# bc-cpu.net
KiCad netlist of a schematic drawn in EAGLE
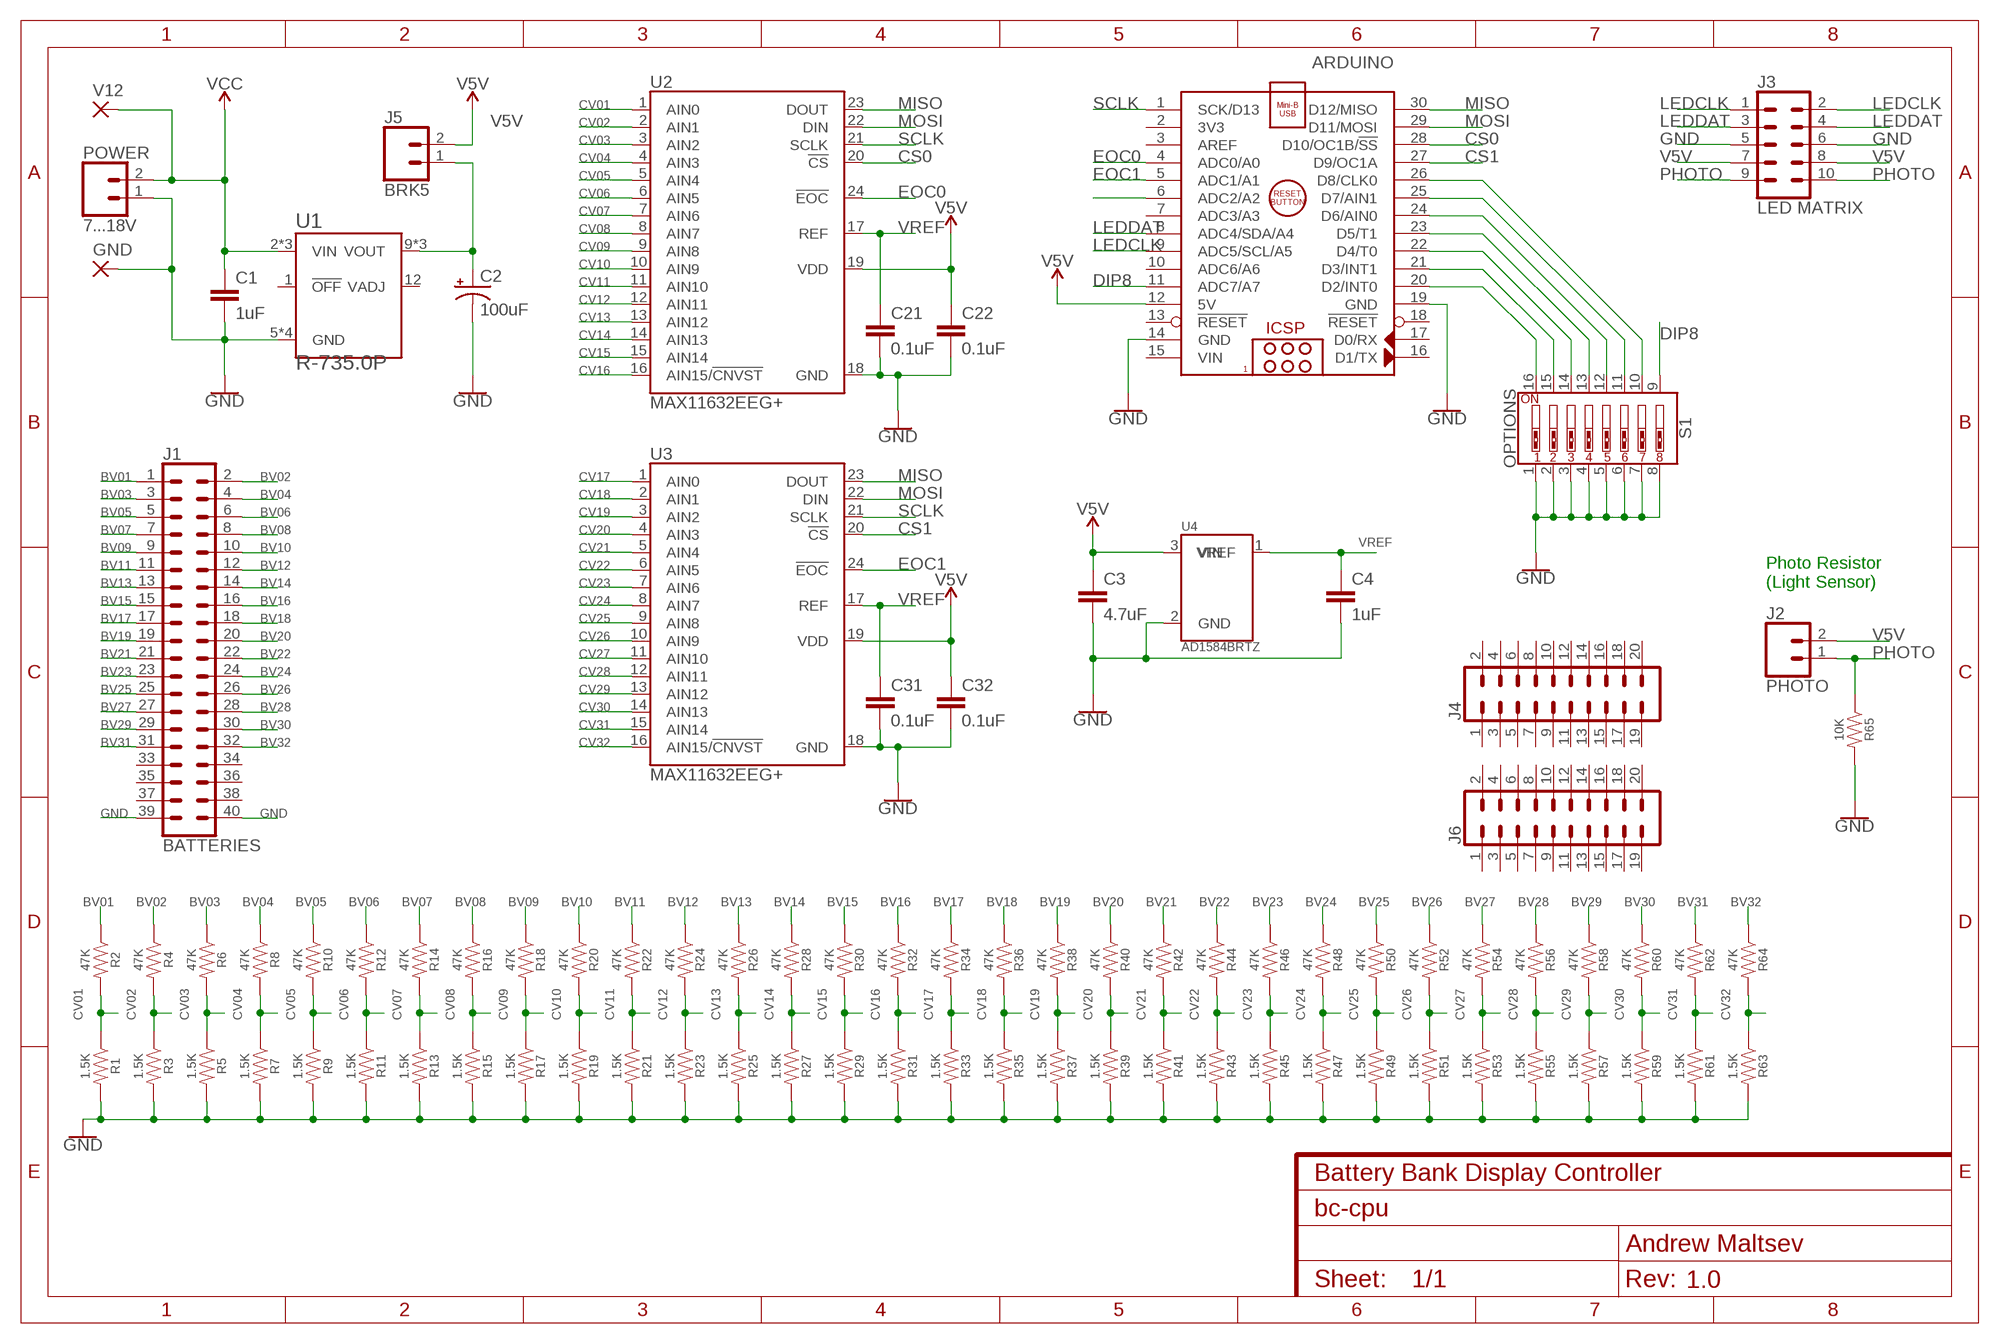
[diagram p0: schematic, sheet 1]

(export (version "E")
  (design (tool "Eeschema 10.0.6"))
  (components
    (comp (ref "ARDUINO")
      (value "ARDUINO_NANO")
      (footprint "eagle-import:ARDUINO_NANO")
      (libsource (lib "eagle-import") (part "ARDUINO_NANO"))
    )
    (comp (ref "C1")
      (value "1uF")
      (footprint "eagle-import:C5B3")
      (libsource (lib "eagle-import") (part "C5/3"))
    )
    (comp (ref "C2")
      (value "100uF")
      (footprint "eagle-import:CPOL-RADIAL-2.5MM-6.5MM")
      (libsource (lib "eagle-import") (part "100UF-POLAR-RADIAL-2.5MM-25V-20%"))
    )
    (comp (ref "C3")
      (value "4.7uF")
      (footprint "eagle-import:C5B3")
      (libsource (lib "eagle-import") (part "C5/3"))
    )
    (comp (ref "C4")
      (value "1uF")
      (footprint "eagle-import:C5B3")
      (libsource (lib "eagle-import") (part "C5/3"))
    )
    (comp (ref "C21")
      (value "0.1uF")
      (footprint "eagle-import:C5B3")
      (libsource (lib "eagle-import") (part "C5/3"))
    )
    (comp (ref "C22")
      (value "0.1uF")
      (footprint "eagle-import:C5B3")
      (libsource (lib "eagle-import") (part "C5/3"))
    )
    (comp (ref "C31")
      (value "0.1uF")
      (footprint "eagle-import:C5B3")
      (libsource (lib "eagle-import") (part "C5/3"))
    )
    (comp (ref "C32")
      (value "0.1uF")
      (footprint "eagle-import:C5B3")
      (libsource (lib "eagle-import") (part "C5/3"))
    )
    (comp (ref "GND")
      (value "WIREPAD3,17/1,2")
      (footprint "eagle-import:3,17_1,2")
      (libsource (lib "eagle-import") (part "WIREPAD3,17/1,2"))
    )
    (comp (ref "J1")
      (value "BATTERIES")
      (footprint "eagle-import:2X20_SHROUDED")
      (libsource (lib "eagle-import") (part "CONN_20X2SHROUDED"))
    )
    (comp (ref "J2")
      (value "PHOTO")
      (footprint "eagle-import:1X02")
      (libsource (lib "eagle-import") (part "CONN_02"))
    )
    (comp (ref "J3")
      (value "LED MATRIX")
      (footprint "eagle-import:2X5-SHROUDED")
      (libsource (lib "eagle-import") (part "CONN_05X2SHD"))
    )
    (comp (ref "J4")
      (value "CONN_10X2NOSILK")
      (footprint "eagle-import:2X10_NOSILK")
      (libsource (lib "eagle-import") (part "CONN_10X2NOSILK"))
    )
    (comp (ref "J5")
      (value "BRK5")
      (footprint "eagle-import:1X02")
      (libsource (lib "eagle-import") (part "CONN_02"))
    )
    (comp (ref "J6")
      (value "CONN_10X2NOSILK")
      (footprint "eagle-import:2X10_NOSILK")
      (libsource (lib "eagle-import") (part "CONN_10X2NOSILK"))
    )
    (comp (ref "POWER")
      (value "7...18V")
      (footprint "eagle-import:1X02")
      (libsource (lib "eagle-import") (part "CONN_02"))
    )
    (comp (ref "R1")
      (value "1.5K")
      (footprint "eagle-import:1206")
      (libsource (lib "eagle-import") (part "RESISTOR1206"))
    )
    (comp (ref "R2")
      (value "47K")
      (footprint "eagle-import:1206")
      (libsource (lib "eagle-import") (part "RESISTOR1206"))
    )
    (comp (ref "R3")
      (value "1.5K")
      (footprint "eagle-import:1206")
      (libsource (lib "eagle-import") (part "RESISTOR1206"))
    )
    (comp (ref "R4")
      (value "47K")
      (footprint "eagle-import:1206")
      (libsource (lib "eagle-import") (part "RESISTOR1206"))
    )
    (comp (ref "R5")
      (value "1.5K")
      (footprint "eagle-import:1206")
      (libsource (lib "eagle-import") (part "RESISTOR1206"))
    )
    (comp (ref "R6")
      (value "47K")
      (footprint "eagle-import:1206")
      (libsource (lib "eagle-import") (part "RESISTOR1206"))
    )
    (comp (ref "R7")
      (value "1.5K")
      (footprint "eagle-import:1206")
      (libsource (lib "eagle-import") (part "RESISTOR1206"))
    )
    (comp (ref "R8")
      (value "47K")
      (footprint "eagle-import:1206")
      (libsource (lib "eagle-import") (part "RESISTOR1206"))
    )
    (comp (ref "R9")
      (value "1.5K")
      (footprint "eagle-import:1206")
      (libsource (lib "eagle-import") (part "RESISTOR1206"))
    )
    (comp (ref "R10")
      (value "47K")
      (footprint "eagle-import:1206")
      (libsource (lib "eagle-import") (part "RESISTOR1206"))
    )
    (comp (ref "R11")
      (value "1.5K")
      (footprint "eagle-import:1206")
      (libsource (lib "eagle-import") (part "RESISTOR1206"))
    )
    (comp (ref "R12")
      (value "47K")
      (footprint "eagle-import:1206")
      (libsource (lib "eagle-import") (part "RESISTOR1206"))
    )
    (comp (ref "R13")
      (value "1.5K")
      (footprint "eagle-import:1206")
      (libsource (lib "eagle-import") (part "RESISTOR1206"))
    )
    (comp (ref "R14")
      (value "47K")
      (footprint "eagle-import:1206")
      (libsource (lib "eagle-import") (part "RESISTOR1206"))
    )
    (comp (ref "R15")
      (value "1.5K")
      (footprint "eagle-import:1206")
      (libsource (lib "eagle-import") (part "RESISTOR1206"))
    )
    (comp (ref "R16")
      (value "47K")
      (footprint "eagle-import:1206")
      (libsource (lib "eagle-import") (part "RESISTOR1206"))
    )
    (comp (ref "R17")
      (value "1.5K")
      (footprint "eagle-import:1206")
      (libsource (lib "eagle-import") (part "RESISTOR1206"))
    )
    (comp (ref "R18")
      (value "47K")
      (footprint "eagle-import:1206")
      (libsource (lib "eagle-import") (part "RESISTOR1206"))
    )
    (comp (ref "R19")
      (value "1.5K")
      (footprint "eagle-import:1206")
      (libsource (lib "eagle-import") (part "RESISTOR1206"))
    )
    (comp (ref "R20")
      (value "47K")
      (footprint "eagle-import:1206")
      (libsource (lib "eagle-import") (part "RESISTOR1206"))
    )
    (comp (ref "R21")
      (value "1.5K")
      (footprint "eagle-import:1206")
      (libsource (lib "eagle-import") (part "RESISTOR1206"))
    )
    (comp (ref "R22")
      (value "47K")
      (footprint "eagle-import:1206")
      (libsource (lib "eagle-import") (part "RESISTOR1206"))
    )
    (comp (ref "R23")
      (value "1.5K")
      (footprint "eagle-import:1206")
      (libsource (lib "eagle-import") (part "RESISTOR1206"))
    )
    (comp (ref "R24")
      (value "47K")
      (footprint "eagle-import:1206")
      (libsource (lib "eagle-import") (part "RESISTOR1206"))
    )
    (comp (ref "R25")
      (value "1.5K")
      (footprint "eagle-import:1206")
      (libsource (lib "eagle-import") (part "RESISTOR1206"))
    )
    (comp (ref "R26")
      (value "47K")
      (footprint "eagle-import:1206")
      (libsource (lib "eagle-import") (part "RESISTOR1206"))
    )
    (comp (ref "R27")
      (value "1.5K")
      (footprint "eagle-import:1206")
      (libsource (lib "eagle-import") (part "RESISTOR1206"))
    )
    (comp (ref "R28")
      (value "47K")
      (footprint "eagle-import:1206")
      (libsource (lib "eagle-import") (part "RESISTOR1206"))
    )
    (comp (ref "R29")
      (value "1.5K")
      (footprint "eagle-import:1206")
      (libsource (lib "eagle-import") (part "RESISTOR1206"))
    )
    (comp (ref "R30")
      (value "47K")
      (footprint "eagle-import:1206")
      (libsource (lib "eagle-import") (part "RESISTOR1206"))
    )
    (comp (ref "R31")
      (value "1.5K")
      (footprint "eagle-import:1206")
      (libsource (lib "eagle-import") (part "RESISTOR1206"))
    )
    (comp (ref "R32")
      (value "47K")
      (footprint "eagle-import:1206")
      (libsource (lib "eagle-import") (part "RESISTOR1206"))
    )
    (comp (ref "R33")
      (value "1.5K")
      (footprint "eagle-import:1206")
      (libsource (lib "eagle-import") (part "RESISTOR1206"))
    )
    (comp (ref "R34")
      (value "47K")
      (footprint "eagle-import:1206")
      (libsource (lib "eagle-import") (part "RESISTOR1206"))
    )
    (comp (ref "R35")
      (value "1.5K")
      (footprint "eagle-import:1206")
      (libsource (lib "eagle-import") (part "RESISTOR1206"))
    )
    (comp (ref "R36")
      (value "47K")
      (footprint "eagle-import:1206")
      (libsource (lib "eagle-import") (part "RESISTOR1206"))
    )
    (comp (ref "R37")
      (value "1.5K")
      (footprint "eagle-import:1206")
      (libsource (lib "eagle-import") (part "RESISTOR1206"))
    )
    (comp (ref "R38")
      (value "47K")
      (footprint "eagle-import:1206")
      (libsource (lib "eagle-import") (part "RESISTOR1206"))
    )
    (comp (ref "R39")
      (value "1.5K")
      (footprint "eagle-import:1206")
      (libsource (lib "eagle-import") (part "RESISTOR1206"))
    )
    (comp (ref "R40")
      (value "47K")
      (footprint "eagle-import:1206")
      (libsource (lib "eagle-import") (part "RESISTOR1206"))
    )
    (comp (ref "R41")
      (value "1.5K")
      (footprint "eagle-import:1206")
      (libsource (lib "eagle-import") (part "RESISTOR1206"))
    )
    (comp (ref "R42")
      (value "47K")
      (footprint "eagle-import:1206")
      (libsource (lib "eagle-import") (part "RESISTOR1206"))
    )
    (comp (ref "R43")
      (value "1.5K")
      (footprint "eagle-import:1206")
      (libsource (lib "eagle-import") (part "RESISTOR1206"))
    )
    (comp (ref "R44")
      (value "47K")
      (footprint "eagle-import:1206")
      (libsource (lib "eagle-import") (part "RESISTOR1206"))
    )
    (comp (ref "R45")
      (value "1.5K")
      (footprint "eagle-import:1206")
      (libsource (lib "eagle-import") (part "RESISTOR1206"))
    )
    (comp (ref "R46")
      (value "47K")
      (footprint "eagle-import:1206")
      (libsource (lib "eagle-import") (part "RESISTOR1206"))
    )
    (comp (ref "R47")
      (value "1.5K")
      (footprint "eagle-import:1206")
      (libsource (lib "eagle-import") (part "RESISTOR1206"))
    )
    (comp (ref "R48")
      (value "47K")
      (footprint "eagle-import:1206")
      (libsource (lib "eagle-import") (part "RESISTOR1206"))
    )
    (comp (ref "R49")
      (value "1.5K")
      (footprint "eagle-import:1206")
      (libsource (lib "eagle-import") (part "RESISTOR1206"))
    )
    (comp (ref "R50")
      (value "47K")
      (footprint "eagle-import:1206")
      (libsource (lib "eagle-import") (part "RESISTOR1206"))
    )
    (comp (ref "R51")
      (value "1.5K")
      (footprint "eagle-import:1206")
      (libsource (lib "eagle-import") (part "RESISTOR1206"))
    )
    (comp (ref "R52")
      (value "47K")
      (footprint "eagle-import:1206")
      (libsource (lib "eagle-import") (part "RESISTOR1206"))
    )
    (comp (ref "R53")
      (value "1.5K")
      (footprint "eagle-import:1206")
      (libsource (lib "eagle-import") (part "RESISTOR1206"))
    )
    (comp (ref "R54")
      (value "47K")
      (footprint "eagle-import:1206")
      (libsource (lib "eagle-import") (part "RESISTOR1206"))
    )
    (comp (ref "R55")
      (value "1.5K")
      (footprint "eagle-import:1206")
      (libsource (lib "eagle-import") (part "RESISTOR1206"))
    )
    (comp (ref "R56")
      (value "47K")
      (footprint "eagle-import:1206")
      (libsource (lib "eagle-import") (part "RESISTOR1206"))
    )
    (comp (ref "R57")
      (value "1.5K")
      (footprint "eagle-import:1206")
      (libsource (lib "eagle-import") (part "RESISTOR1206"))
    )
    (comp (ref "R58")
      (value "47K")
      (footprint "eagle-import:1206")
      (libsource (lib "eagle-import") (part "RESISTOR1206"))
    )
    (comp (ref "R59")
      (value "1.5K")
      (footprint "eagle-import:1206")
      (libsource (lib "eagle-import") (part "RESISTOR1206"))
    )
    (comp (ref "R60")
      (value "47K")
      (footprint "eagle-import:1206")
      (libsource (lib "eagle-import") (part "RESISTOR1206"))
    )
    (comp (ref "R61")
      (value "1.5K")
      (footprint "eagle-import:1206")
      (libsource (lib "eagle-import") (part "RESISTOR1206"))
    )
    (comp (ref "R62")
      (value "47K")
      (footprint "eagle-import:1206")
      (libsource (lib "eagle-import") (part "RESISTOR1206"))
    )
    (comp (ref "R63")
      (value "1.5K")
      (footprint "eagle-import:1206")
      (libsource (lib "eagle-import") (part "RESISTOR1206"))
    )
    (comp (ref "R64")
      (value "47K")
      (footprint "eagle-import:1206")
      (libsource (lib "eagle-import") (part "RESISTOR1206"))
    )
    (comp (ref "R65")
      (value "10K")
      (footprint "eagle-import:AXIAL-0.3")
      (libsource (lib "eagle-import") (part "RESISTORAXIAL-0.3"))
    )
    (comp (ref "S1")
      (value "OPTIONS")
      (footprint "eagle-import:DIPSWITCH-08")
      (libsource (lib "eagle-import") (part "DIP-08-PTH"))
    )
    (comp (ref "U1")
      (value "R-735.0P")
      (footprint "eagle-import:RECOM-R-7XX.XX")
      (libsource (lib "eagle-import") (part "RECOM-R-7XX.XXPTH"))
    )
    (comp (ref "U2")
      (value "MAX11632EEG+")
      (footprint "eagle-import:QSOP24")
      (libsource (lib "eagle-import") (part "MAX-11632QSOP24"))
    )
    (comp (ref "U3")
      (value "MAX11632EEG+")
      (footprint "eagle-import:QSOP24")
      (libsource (lib "eagle-import") (part "MAX-11632QSOP24"))
    )
    (comp (ref "U4")
      (value "AD1584BRTZ")
      (footprint "eagle-import:SOT23-3")
      (libsource (lib "eagle-import") (part "AD1582"))
    )
    (comp (ref "V12")
      (value "WIREPAD3,17/1,2")
      (footprint "eagle-import:3,17_1,2")
      (libsource (lib "eagle-import") (part "WIREPAD3,17/1,2"))
    )
  )
  (nets
    (net (code "1") (name "/BV01") (class "Default")
      (node (ref "J1") (pin "1") (pinfunction "1_1") (pintype "passive"))
      (node (ref "R2") (pin "1") (pinfunction "1_1") (pintype "passive"))
    )
    (net (code "2") (name "/BV02") (class "Default")
      (node (ref "J1") (pin "2") (pinfunction "2_2") (pintype "passive"))
      (node (ref "R4") (pin "1") (pinfunction "1_1") (pintype "passive"))
    )
    (net (code "3") (name "/BV03") (class "Default")
      (node (ref "J1") (pin "3") (pinfunction "3_3") (pintype "passive"))
      (node (ref "R6") (pin "1") (pinfunction "1_1") (pintype "passive"))
    )
    (net (code "4") (name "/BV04") (class "Default")
      (node (ref "J1") (pin "4") (pinfunction "4_4") (pintype "passive"))
      (node (ref "R8") (pin "1") (pinfunction "1_1") (pintype "passive"))
    )
    (net (code "5") (name "/BV05") (class "Default")
      (node (ref "J1") (pin "5") (pinfunction "5_5") (pintype "passive"))
      (node (ref "R10") (pin "1") (pinfunction "1_1") (pintype "passive"))
    )
    (net (code "6") (name "/BV06") (class "Default")
      (node (ref "J1") (pin "6") (pinfunction "6_6") (pintype "passive"))
      (node (ref "R12") (pin "1") (pinfunction "1_1") (pintype "passive"))
    )
    (net (code "7") (name "/BV07") (class "Default")
      (node (ref "J1") (pin "7") (pinfunction "7_7") (pintype "passive"))
      (node (ref "R14") (pin "1") (pinfunction "1_1") (pintype "passive"))
    )
    (net (code "8") (name "/BV08") (class "Default")
      (node (ref "J1") (pin "8") (pinfunction "8_8") (pintype "passive"))
      (node (ref "R16") (pin "1") (pinfunction "1_1") (pintype "passive"))
    )
    (net (code "9") (name "/BV09") (class "Default")
      (node (ref "J1") (pin "9") (pinfunction "9_9") (pintype "passive"))
      (node (ref "R18") (pin "1") (pinfunction "1_1") (pintype "passive"))
    )
    (net (code "10") (name "/BV10") (class "Default")
      (node (ref "J1") (pin "10") (pinfunction "10_10") (pintype "passive"))
      (node (ref "R20") (pin "1") (pinfunction "1_1") (pintype "passive"))
    )
    (net (code "11") (name "/BV11") (class "Default")
      (node (ref "J1") (pin "11") (pinfunction "11_11") (pintype "passive"))
      (node (ref "R22") (pin "1") (pinfunction "1_1") (pintype "passive"))
    )
    (net (code "12") (name "/BV12") (class "Default")
      (node (ref "J1") (pin "12") (pinfunction "12_12") (pintype "passive"))
      (node (ref "R24") (pin "1") (pinfunction "1_1") (pintype "passive"))
    )
    (net (code "13") (name "/BV13") (class "Default")
      (node (ref "J1") (pin "13") (pinfunction "13_13") (pintype "passive"))
      (node (ref "R26") (pin "1") (pinfunction "1_1") (pintype "passive"))
    )
    (net (code "14") (name "/BV14") (class "Default")
      (node (ref "J1") (pin "14") (pinfunction "14_14") (pintype "passive"))
      (node (ref "R28") (pin "1") (pinfunction "1_1") (pintype "passive"))
    )
    (net (code "15") (name "/BV15") (class "Default")
      (node (ref "J1") (pin "15") (pinfunction "15_15") (pintype "passive"))
      (node (ref "R30") (pin "1") (pinfunction "1_1") (pintype "passive"))
    )
    (net (code "16") (name "/BV16") (class "Default")
      (node (ref "J1") (pin "16") (pinfunction "16_16") (pintype "passive"))
      (node (ref "R32") (pin "1") (pinfunction "1_1") (pintype "passive"))
    )
    (net (code "17") (name "/BV17") (class "Default")
      (node (ref "J1") (pin "17") (pinfunction "17_17") (pintype "passive"))
      (node (ref "R34") (pin "1") (pinfunction "1_1") (pintype "passive"))
    )
    (net (code "18") (name "/BV18") (class "Default")
      (node (ref "J1") (pin "18") (pinfunction "18_18") (pintype "passive"))
      (node (ref "R36") (pin "1") (pinfunction "1_1") (pintype "passive"))
    )
    (net (code "19") (name "/BV19") (class "Default")
      (node (ref "J1") (pin "19") (pinfunction "19_19") (pintype "passive"))
      (node (ref "R38") (pin "1") (pinfunction "1_1") (pintype "passive"))
    )
    (net (code "20") (name "/BV20") (class "Default")
      (node (ref "J1") (pin "20") (pinfunction "20_20") (pintype "passive"))
      (node (ref "R40") (pin "1") (pinfunction "1_1") (pintype "passive"))
    )
    (net (code "21") (name "/BV21") (class "Default")
      (node (ref "J1") (pin "21") (pinfunction "21_21") (pintype "passive"))
      (node (ref "R42") (pin "1") (pinfunction "1_1") (pintype "passive"))
    )
    (net (code "22") (name "/BV22") (class "Default")
      (node (ref "J1") (pin "22") (pinfunction "22_22") (pintype "passive"))
      (node (ref "R44") (pin "1") (pinfunction "1_1") (pintype "passive"))
    )
    (net (code "23") (name "/BV23") (class "Default")
      (node (ref "J1") (pin "23") (pinfunction "23_23") (pintype "passive"))
      (node (ref "R46") (pin "1") (pinfunction "1_1") (pintype "passive"))
    )
    (net (code "24") (name "/BV24") (class "Default")
      (node (ref "J1") (pin "24") (pinfunction "24_24") (pintype "passive"))
      (node (ref "R48") (pin "1") (pinfunction "1_1") (pintype "passive"))
    )
    (net (code "25") (name "/BV25") (class "Default")
      (node (ref "J1") (pin "25") (pinfunction "25_25") (pintype "passive"))
      (node (ref "R50") (pin "1") (pinfunction "1_1") (pintype "passive"))
    )
    (net (code "26") (name "/BV26") (class "Default")
      (node (ref "J1") (pin "26") (pinfunction "26_26") (pintype "passive"))
      (node (ref "R52") (pin "1") (pinfunction "1_1") (pintype "passive"))
    )
    (net (code "27") (name "/BV27") (class "Default")
      (node (ref "J1") (pin "27") (pinfunction "27_27") (pintype "passive"))
      (node (ref "R54") (pin "1") (pinfunction "1_1") (pintype "passive"))
    )
    (net (code "28") (name "/BV28") (class "Default")
      (node (ref "J1") (pin "28") (pinfunction "28_28") (pintype "passive"))
      (node (ref "R56") (pin "1") (pinfunction "1_1") (pintype "passive"))
    )
    (net (code "29") (name "/BV29") (class "Default")
      (node (ref "J1") (pin "29") (pinfunction "29_29") (pintype "passive"))
      (node (ref "R58") (pin "1") (pinfunction "1_1") (pintype "passive"))
    )
    (net (code "30") (name "/BV30") (class "Default")
      (node (ref "J1") (pin "30") (pinfunction "30_30") (pintype "passive"))
      (node (ref "R60") (pin "1") (pinfunction "1_1") (pintype "passive"))
    )
    (net (code "31") (name "/BV31") (class "Default")
      (node (ref "J1") (pin "31") (pinfunction "31_31") (pintype "passive"))
      (node (ref "R62") (pin "1") (pinfunction "1_1") (pintype "passive"))
    )
    (net (code "32") (name "/BV32") (class "Default")
      (node (ref "J1") (pin "32") (pinfunction "32_32") (pintype "passive"))
      (node (ref "R64") (pin "1") (pinfunction "1_1") (pintype "passive"))
    )
    (net (code "33") (name "/CS0") (class "Default")
      (node (ref "ARDUINO") (pin "28") (pinfunction "D10/OC1B/~{SS}_28") (pintype "bidirectional"))
      (node (ref "U2") (pin "20") (pinfunction "~{CS}_20") (pintype "bidirectional"))
    )
    (net (code "34") (name "/CS1") (class "Default")
      (node (ref "ARDUINO") (pin "27") (pinfunction "D9/OC1A_27") (pintype "bidirectional"))
      (node (ref "U3") (pin "20") (pinfunction "~{CS}_20") (pintype "bidirectional"))
    )
    (net (code "35") (name "/CV01") (class "Default")
      (node (ref "R1") (pin "1") (pinfunction "1_1") (pintype "passive"))
      (node (ref "R2") (pin "2") (pinfunction "2_2") (pintype "passive"))
      (node (ref "U2") (pin "1") (pinfunction "AIN0_1") (pintype "input"))
    )
    (net (code "36") (name "/CV02") (class "Default")
      (node (ref "R3") (pin "1") (pinfunction "1_1") (pintype "passive"))
      (node (ref "R4") (pin "2") (pinfunction "2_2") (pintype "passive"))
      (node (ref "U2") (pin "2") (pinfunction "AIN1_2") (pintype "input"))
    )
    (net (code "37") (name "/CV03") (class "Default")
      (node (ref "R5") (pin "1") (pinfunction "1_1") (pintype "passive"))
      (node (ref "R6") (pin "2") (pinfunction "2_2") (pintype "passive"))
      (node (ref "U2") (pin "3") (pinfunction "AIN2_3") (pintype "input"))
    )
    (net (code "38") (name "/CV04") (class "Default")
      (node (ref "R7") (pin "1") (pinfunction "1_1") (pintype "passive"))
      (node (ref "R8") (pin "2") (pinfunction "2_2") (pintype "passive"))
      (node (ref "U2") (pin "4") (pinfunction "AIN3_4") (pintype "input"))
    )
    (net (code "39") (name "/CV05") (class "Default")
      (node (ref "R10") (pin "2") (pinfunction "2_2") (pintype "passive"))
      (node (ref "R9") (pin "1") (pinfunction "1_1") (pintype "passive"))
      (node (ref "U2") (pin "5") (pinfunction "AIN4_5") (pintype "input"))
    )
    (net (code "40") (name "/CV06") (class "Default")
      (node (ref "R11") (pin "1") (pinfunction "1_1") (pintype "passive"))
      (node (ref "R12") (pin "2") (pinfunction "2_2") (pintype "passive"))
      (node (ref "U2") (pin "6") (pinfunction "AIN5_6") (pintype "input"))
    )
    (net (code "41") (name "/CV07") (class "Default")
      (node (ref "R13") (pin "1") (pinfunction "1_1") (pintype "passive"))
      (node (ref "R14") (pin "2") (pinfunction "2_2") (pintype "passive"))
      (node (ref "U2") (pin "7") (pinfunction "AIN6_7") (pintype "input"))
    )
    (net (code "42") (name "/CV08") (class "Default")
      (node (ref "R15") (pin "1") (pinfunction "1_1") (pintype "passive"))
      (node (ref "R16") (pin "2") (pinfunction "2_2") (pintype "passive"))
      (node (ref "U2") (pin "8") (pinfunction "AIN7_8") (pintype "input"))
    )
    (net (code "43") (name "/CV09") (class "Default")
      (node (ref "R17") (pin "1") (pinfunction "1_1") (pintype "passive"))
      (node (ref "R18") (pin "2") (pinfunction "2_2") (pintype "passive"))
      (node (ref "U2") (pin "9") (pinfunction "AIN8_9") (pintype "input"))
    )
    (net (code "44") (name "/CV10") (class "Default")
      (node (ref "R19") (pin "1") (pinfunction "1_1") (pintype "passive"))
      (node (ref "R20") (pin "2") (pinfunction "2_2") (pintype "passive"))
      (node (ref "U2") (pin "10") (pinfunction "AIN9_10") (pintype "input"))
    )
    (net (code "45") (name "/CV11") (class "Default")
      (node (ref "R21") (pin "1") (pinfunction "1_1") (pintype "passive"))
      (node (ref "R22") (pin "2") (pinfunction "2_2") (pintype "passive"))
      (node (ref "U2") (pin "11") (pinfunction "AIN10_11") (pintype "input"))
    )
    (net (code "46") (name "/CV12") (class "Default")
      (node (ref "R23") (pin "1") (pinfunction "1_1") (pintype "passive"))
      (node (ref "R24") (pin "2") (pinfunction "2_2") (pintype "passive"))
      (node (ref "U2") (pin "12") (pinfunction "AIN11_12") (pintype "input"))
    )
    (net (code "47") (name "/CV13") (class "Default")
      (node (ref "R25") (pin "1") (pinfunction "1_1") (pintype "passive"))
      (node (ref "R26") (pin "2") (pinfunction "2_2") (pintype "passive"))
      (node (ref "U2") (pin "13") (pinfunction "AIN12_13") (pintype "input"))
    )
    (net (code "48") (name "/CV14") (class "Default")
      (node (ref "R27") (pin "1") (pinfunction "1_1") (pintype "passive"))
      (node (ref "R28") (pin "2") (pinfunction "2_2") (pintype "passive"))
      (node (ref "U2") (pin "14") (pinfunction "AIN13_14") (pintype "input"))
    )
    (net (code "49") (name "/CV15") (class "Default")
      (node (ref "R29") (pin "1") (pinfunction "1_1") (pintype "passive"))
      (node (ref "R30") (pin "2") (pinfunction "2_2") (pintype "passive"))
      (node (ref "U2") (pin "15") (pinfunction "AIN14_15") (pintype "input"))
    )
    (net (code "50") (name "/CV16") (class "Default")
      (node (ref "R31") (pin "1") (pinfunction "1_1") (pintype "passive"))
      (node (ref "R32") (pin "2") (pinfunction "2_2") (pintype "passive"))
      (node (ref "U2") (pin "16") (pinfunction "AIN15/~{CNVST}_16") (pintype "input"))
    )
    (net (code "51") (name "/CV17") (class "Default")
      (node (ref "R33") (pin "1") (pinfunction "1_1") (pintype "passive"))
      (node (ref "R34") (pin "2") (pinfunction "2_2") (pintype "passive"))
      (node (ref "U3") (pin "1") (pinfunction "AIN0_1") (pintype "input"))
    )
    (net (code "52") (name "/CV18") (class "Default")
      (node (ref "R35") (pin "1") (pinfunction "1_1") (pintype "passive"))
      (node (ref "R36") (pin "2") (pinfunction "2_2") (pintype "passive"))
      (node (ref "U3") (pin "2") (pinfunction "AIN1_2") (pintype "input"))
    )
    (net (code "53") (name "/CV19") (class "Default")
      (node (ref "R37") (pin "1") (pinfunction "1_1") (pintype "passive"))
      (node (ref "R38") (pin "2") (pinfunction "2_2") (pintype "passive"))
      (node (ref "U3") (pin "3") (pinfunction "AIN2_3") (pintype "input"))
    )
    (net (code "54") (name "/CV20") (class "Default")
      (node (ref "R39") (pin "1") (pinfunction "1_1") (pintype "passive"))
      (node (ref "R40") (pin "2") (pinfunction "2_2") (pintype "passive"))
      (node (ref "U3") (pin "4") (pinfunction "AIN3_4") (pintype "input"))
    )
    (net (code "55") (name "/CV21") (class "Default")
      (node (ref "R41") (pin "1") (pinfunction "1_1") (pintype "passive"))
      (node (ref "R42") (pin "2") (pinfunction "2_2") (pintype "passive"))
      (node (ref "U3") (pin "5") (pinfunction "AIN4_5") (pintype "input"))
    )
    (net (code "56") (name "/CV22") (class "Default")
      (node (ref "R43") (pin "1") (pinfunction "1_1") (pintype "passive"))
      (node (ref "R44") (pin "2") (pinfunction "2_2") (pintype "passive"))
      (node (ref "U3") (pin "6") (pinfunction "AIN5_6") (pintype "input"))
    )
    (net (code "57") (name "/CV23") (class "Default")
      (node (ref "R45") (pin "1") (pinfunction "1_1") (pintype "passive"))
      (node (ref "R46") (pin "2") (pinfunction "2_2") (pintype "passive"))
      (node (ref "U3") (pin "7") (pinfunction "AIN6_7") (pintype "input"))
    )
    (net (code "58") (name "/CV24") (class "Default")
      (node (ref "R47") (pin "1") (pinfunction "1_1") (pintype "passive"))
      (node (ref "R48") (pin "2") (pinfunction "2_2") (pintype "passive"))
      (node (ref "U3") (pin "8") (pinfunction "AIN7_8") (pintype "input"))
    )
    (net (code "59") (name "/CV25") (class "Default")
      (node (ref "R49") (pin "1") (pinfunction "1_1") (pintype "passive"))
      (node (ref "R50") (pin "2") (pinfunction "2_2") (pintype "passive"))
      (node (ref "U3") (pin "9") (pinfunction "AIN8_9") (pintype "input"))
    )
    (net (code "60") (name "/CV26") (class "Default")
      (node (ref "R51") (pin "1") (pinfunction "1_1") (pintype "passive"))
      (node (ref "R52") (pin "2") (pinfunction "2_2") (pintype "passive"))
      (node (ref "U3") (pin "10") (pinfunction "AIN9_10") (pintype "input"))
    )
    (net (code "61") (name "/CV27") (class "Default")
      (node (ref "R53") (pin "1") (pinfunction "1_1") (pintype "passive"))
      (node (ref "R54") (pin "2") (pinfunction "2_2") (pintype "passive"))
      (node (ref "U3") (pin "11") (pinfunction "AIN10_11") (pintype "input"))
    )
    (net (code "62") (name "/CV28") (class "Default")
      (node (ref "R55") (pin "1") (pinfunction "1_1") (pintype "passive"))
      (node (ref "R56") (pin "2") (pinfunction "2_2") (pintype "passive"))
      (node (ref "U3") (pin "12") (pinfunction "AIN11_12") (pintype "input"))
    )
    (net (code "63") (name "/CV29") (class "Default")
      (node (ref "R57") (pin "1") (pinfunction "1_1") (pintype "passive"))
      (node (ref "R58") (pin "2") (pinfunction "2_2") (pintype "passive"))
      (node (ref "U3") (pin "13") (pinfunction "AIN12_13") (pintype "input"))
    )
    (net (code "64") (name "/CV30") (class "Default")
      (node (ref "R59") (pin "1") (pinfunction "1_1") (pintype "passive"))
      (node (ref "R60") (pin "2") (pinfunction "2_2") (pintype "passive"))
      (node (ref "U3") (pin "14") (pinfunction "AIN13_14") (pintype "input"))
    )
    (net (code "65") (name "/CV31") (class "Default")
      (node (ref "R61") (pin "1") (pinfunction "1_1") (pintype "passive"))
      (node (ref "R62") (pin "2") (pinfunction "2_2") (pintype "passive"))
      (node (ref "U3") (pin "15") (pinfunction "AIN14_15") (pintype "input"))
    )
    (net (code "66") (name "/CV32") (class "Default")
      (node (ref "R63") (pin "1") (pinfunction "1_1") (pintype "passive"))
      (node (ref "R64") (pin "2") (pinfunction "2_2") (pintype "passive"))
      (node (ref "U3") (pin "16") (pinfunction "AIN15/~{CNVST}_16") (pintype "input"))
    )
    (net (code "67") (name "/DIP8") (class "Default")
      (node (ref "ARDUINO") (pin "11") (pinfunction "ADC7/A7_11") (pintype "bidirectional"))
      (node (ref "S1") (pin "9") (pinfunction "9_9") (pintype "passive"))
    )
    (net (code "68") (name "/EOC0") (class "Default")
      (node (ref "ARDUINO") (pin "4") (pinfunction "ADC0/A0_4") (pintype "bidirectional"))
      (node (ref "U2") (pin "24") (pinfunction "~{EOC}_24") (pintype "output"))
    )
    (net (code "69") (name "/EOC1") (class "Default")
      (node (ref "ARDUINO") (pin "5") (pinfunction "ADC1/A1_5") (pintype "bidirectional"))
      (node (ref "U3") (pin "24") (pinfunction "~{EOC}_24") (pintype "output"))
    )
    (net (code "70") (name "/LEDCLK") (class "Default")
      (node (ref "ARDUINO") (pin "9") (pinfunction "ADC5/SCL/A5_9") (pintype "bidirectional"))
      (node (ref "J3") (pin "1") (pinfunction "1_1") (pintype "passive"))
      (node (ref "J3") (pin "2") (pinfunction "2_2") (pintype "passive"))
    )
    (net (code "71") (name "/LEDDAT") (class "Default")
      (node (ref "ARDUINO") (pin "8") (pinfunction "ADC4/SDA/A4_8") (pintype "bidirectional"))
      (node (ref "J3") (pin "3") (pinfunction "3_3") (pintype "passive"))
      (node (ref "J3") (pin "4") (pinfunction "4_4") (pintype "passive"))
    )
    (net (code "72") (name "/MISO") (class "Default")
      (node (ref "ARDUINO") (pin "30") (pinfunction "D12/MISO_30") (pintype "bidirectional"))
      (node (ref "U2") (pin "23") (pinfunction "DOUT_23") (pintype "bidirectional"))
      (node (ref "U3") (pin "23") (pinfunction "DOUT_23") (pintype "bidirectional"))
    )
    (net (code "73") (name "/MOSI") (class "Default")
      (node (ref "ARDUINO") (pin "29") (pinfunction "D11/MOSI_29") (pintype "bidirectional"))
      (node (ref "U2") (pin "22") (pinfunction "DIN_22") (pintype "bidirectional"))
      (node (ref "U3") (pin "22") (pinfunction "DIN_22") (pintype "bidirectional"))
    )
    (net (code "74") (name "/PHOTO") (class "Default")
      (node (ref "ARDUINO") (pin "6") (pinfunction "ADC2/A2_6") (pintype "bidirectional"))
      (node (ref "J2") (pin "1") (pinfunction "1_1") (pintype "passive"))
      (node (ref "J3") (pin "10") (pinfunction "10_10") (pintype "passive"))
      (node (ref "J3") (pin "9") (pinfunction "9_9") (pintype "passive"))
      (node (ref "R65") (pin "P$1") (pinfunction "1_P$1") (pintype "passive"))
    )
    (net (code "75") (name "/SCLK") (class "Default")
      (node (ref "ARDUINO") (pin "1") (pinfunction "SCK/D13_1") (pintype "bidirectional"))
      (node (ref "U2") (pin "21") (pinfunction "SCLK_21") (pintype "bidirectional"))
      (node (ref "U3") (pin "21") (pinfunction "SCLK_21") (pintype "bidirectional"))
    )
    (net (code "76") (name "/VIN") (class "Default")
      (node (ref "ARDUINO") (pin "15") (pinfunction "VIN_15") (pintype "power_in"))
    )
    (net (code "77") (name "/VREF") (class "Default")
      (node (ref "C21") (pin "1") (pinfunction "1_1") (pintype "passive"))
      (node (ref "C31") (pin "1") (pinfunction "1_1") (pintype "passive"))
      (node (ref "C4") (pin "1") (pinfunction "1_1") (pintype "passive"))
      (node (ref "U2") (pin "17") (pinfunction "REF_17") (pintype "bidirectional"))
      (node (ref "U3") (pin "17") (pinfunction "REF_17") (pintype "bidirectional"))
      (node (ref "U4") (pin "1") (pinfunction "VREF_1") (pintype "output"))
    )
    (net (code "78") (name "GND") (class "Default")
      (node (ref "ARDUINO") (pin "14") (pinfunction "GND_14") (pintype "power_in"))
      (node (ref "ARDUINO") (pin "19") (pinfunction "GND_19") (pintype "power_in"))
      (node (ref "C1") (pin "2") (pinfunction "2_2") (pintype "passive"))
      (node (ref "C2") (pin "2") (pinfunction "-_2") (pintype "passive"))
      (node (ref "C21") (pin "2") (pinfunction "2_2") (pintype "passive"))
      (node (ref "C22") (pin "2") (pinfunction "2_2") (pintype "passive"))
      (node (ref "C3") (pin "2") (pinfunction "2_2") (pintype "passive"))
      (node (ref "C31") (pin "2") (pinfunction "2_2") (pintype "passive"))
      (node (ref "C32") (pin "2") (pinfunction "2_2") (pintype "passive"))
      (node (ref "C4") (pin "2") (pinfunction "2_2") (pintype "passive"))
      (node (ref "GND") (pin "1") (pinfunction "P_1") (pintype "passive"))
      (node (ref "J1") (pin "39") (pinfunction "39_39") (pintype "passive"))
      (node (ref "J1") (pin "40") (pinfunction "40_40") (pintype "passive"))
      (node (ref "J3") (pin "5") (pinfunction "5_5") (pintype "passive"))
      (node (ref "J3") (pin "6") (pinfunction "6_6") (pintype "passive"))
      (node (ref "POWER") (pin "1") (pinfunction "1_1") (pintype "passive"))
      (node (ref "R1") (pin "2") (pinfunction "2_2") (pintype "passive"))
      (node (ref "R11") (pin "2") (pinfunction "2_2") (pintype "passive"))
      (node (ref "R13") (pin "2") (pinfunction "2_2") (pintype "passive"))
      (node (ref "R15") (pin "2") (pinfunction "2_2") (pintype "passive"))
      (node (ref "R17") (pin "2") (pinfunction "2_2") (pintype "passive"))
      (node (ref "R19") (pin "2") (pinfunction "2_2") (pintype "passive"))
      (node (ref "R21") (pin "2") (pinfunction "2_2") (pintype "passive"))
      (node (ref "R23") (pin "2") (pinfunction "2_2") (pintype "passive"))
      (node (ref "R25") (pin "2") (pinfunction "2_2") (pintype "passive"))
      (node (ref "R27") (pin "2") (pinfunction "2_2") (pintype "passive"))
      (node (ref "R29") (pin "2") (pinfunction "2_2") (pintype "passive"))
      (node (ref "R3") (pin "2") (pinfunction "2_2") (pintype "passive"))
      (node (ref "R31") (pin "2") (pinfunction "2_2") (pintype "passive"))
      (node (ref "R33") (pin "2") (pinfunction "2_2") (pintype "passive"))
      (node (ref "R35") (pin "2") (pinfunction "2_2") (pintype "passive"))
      (node (ref "R37") (pin "2") (pinfunction "2_2") (pintype "passive"))
      (node (ref "R39") (pin "2") (pinfunction "2_2") (pintype "passive"))
      (node (ref "R41") (pin "2") (pinfunction "2_2") (pintype "passive"))
      (node (ref "R43") (pin "2") (pinfunction "2_2") (pintype "passive"))
      (node (ref "R45") (pin "2") (pinfunction "2_2") (pintype "passive"))
      (node (ref "R47") (pin "2") (pinfunction "2_2") (pintype "passive"))
      (node (ref "R49") (pin "2") (pinfunction "2_2") (pintype "passive"))
      (node (ref "R5") (pin "2") (pinfunction "2_2") (pintype "passive"))
      (node (ref "R51") (pin "2") (pinfunction "2_2") (pintype "passive"))
      (node (ref "R53") (pin "2") (pinfunction "2_2") (pintype "passive"))
      (node (ref "R55") (pin "2") (pinfunction "2_2") (pintype "passive"))
      (node (ref "R57") (pin "2") (pinfunction "2_2") (pintype "passive"))
      (node (ref "R59") (pin "2") (pinfunction "2_2") (pintype "passive"))
      (node (ref "R61") (pin "2") (pinfunction "2_2") (pintype "passive"))
      (node (ref "R63") (pin "2") (pinfunction "2_2") (pintype "passive"))
      (node (ref "R65") (pin "P$2") (pinfunction "2_P$2") (pintype "passive"))
      (node (ref "R7") (pin "2") (pinfunction "2_2") (pintype "passive"))
      (node (ref "R9") (pin "2") (pinfunction "2_2") (pintype "passive"))
      (node (ref "S1") (pin "1") (pinfunction "1_1") (pintype "passive"))
      (node (ref "S1") (pin "2") (pinfunction "2_2") (pintype "passive"))
      (node (ref "S1") (pin "3") (pinfunction "3_3") (pintype "passive"))
      (node (ref "S1") (pin "4") (pinfunction "4_4") (pintype "passive"))
      (node (ref "S1") (pin "5") (pinfunction "5_5") (pintype "passive"))
      (node (ref "S1") (pin "6") (pinfunction "6_6") (pintype "passive"))
      (node (ref "S1") (pin "7") (pinfunction "7_7") (pintype "passive"))
      (node (ref "S1") (pin "8") (pinfunction "8_8") (pintype "passive"))
      (node (ref "U1") (pin "5") (pinfunction "GND_5") (pintype "power_in"))
      (node (ref "U1") (pin "6") (pinfunction "GND_6") (pintype "power_in"))
      (node (ref "U1") (pin "7") (pinfunction "GND_7") (pintype "power_in"))
      (node (ref "U1") (pin "8") (pinfunction "GND_8") (pintype "power_in"))
      (node (ref "U2") (pin "18") (pinfunction "GND_18") (pintype "power_in"))
      (node (ref "U3") (pin "18") (pinfunction "GND_18") (pintype "power_in"))
      (node (ref "U4") (pin "2") (pinfunction "GND_2") (pintype "power_in"))
    )
    (net (code "79") (name "Net-(ARDUINO-D2{slash}INT0)") (class "Default")
      (node (ref "ARDUINO") (pin "20") (pinfunction "D2/INT0_20") (pintype "bidirectional"))
      (node (ref "S1") (pin "16") (pinfunction "16_16") (pintype "passive"))
    )
    (net (code "80") (name "Net-(ARDUINO-D3{slash}INT1)") (class "Default")
      (node (ref "ARDUINO") (pin "21") (pinfunction "D3/INT1_21") (pintype "bidirectional"))
      (node (ref "S1") (pin "15") (pinfunction "15_15") (pintype "passive"))
    )
    (net (code "81") (name "Net-(ARDUINO-D4{slash}T0)") (class "Default")
      (node (ref "ARDUINO") (pin "22") (pinfunction "D4/T0_22") (pintype "bidirectional"))
      (node (ref "S1") (pin "14") (pinfunction "14_14") (pintype "passive"))
    )
    (net (code "82") (name "Net-(ARDUINO-D5{slash}T1)") (class "Default")
      (node (ref "ARDUINO") (pin "23") (pinfunction "D5/T1_23") (pintype "bidirectional"))
      (node (ref "S1") (pin "13") (pinfunction "13_13") (pintype "passive"))
    )
    (net (code "83") (name "Net-(ARDUINO-D6{slash}AIN0)") (class "Default")
      (node (ref "ARDUINO") (pin "24") (pinfunction "D6/AIN0_24") (pintype "bidirectional"))
      (node (ref "S1") (pin "12") (pinfunction "12_12") (pintype "passive"))
    )
    (net (code "84") (name "Net-(ARDUINO-D7{slash}AIN1)") (class "Default")
      (node (ref "ARDUINO") (pin "25") (pinfunction "D7/AIN1_25") (pintype "bidirectional"))
      (node (ref "S1") (pin "11") (pinfunction "11_11") (pintype "passive"))
    )
    (net (code "85") (name "Net-(ARDUINO-D8{slash}CLK0)") (class "Default")
      (node (ref "ARDUINO") (pin "26") (pinfunction "D8/CLK0_26") (pintype "bidirectional"))
      (node (ref "S1") (pin "10") (pinfunction "10_10") (pintype "passive"))
    )
    (net (code "86") (name "Net-(C2-+)") (class "Default")
      (node (ref "C2") (pin "1") (pinfunction "+_1") (pintype "passive"))
      (node (ref "J5") (pin "1") (pinfunction "1_1") (pintype "passive"))
      (node (ref "U1") (pin "10") (pinfunction "VOUT_10") (pintype "power_in"))
      (node (ref "U1") (pin "11") (pinfunction "VOUT_11") (pintype "power_in"))
      (node (ref "U1") (pin "9") (pinfunction "VOUT_9") (pintype "power_in"))
    )
    (net (code "87") (name "V5V") (class "Default")
      (node (ref "ARDUINO") (pin "12") (pinfunction "5V_12") (pintype "power_in"))
      (node (ref "C22") (pin "1") (pinfunction "1_1") (pintype "passive"))
      (node (ref "C3") (pin "1") (pinfunction "1_1") (pintype "passive"))
      (node (ref "C32") (pin "1") (pinfunction "1_1") (pintype "passive"))
      (node (ref "J2") (pin "2") (pinfunction "2_2") (pintype "passive"))
      (node (ref "J3") (pin "7") (pinfunction "7_7") (pintype "passive"))
      (node (ref "J3") (pin "8") (pinfunction "8_8") (pintype "passive"))
      (node (ref "J5") (pin "2") (pinfunction "2_2") (pintype "passive"))
      (node (ref "U2") (pin "19") (pinfunction "VDD_19") (pintype "power_in"))
      (node (ref "U3") (pin "19") (pinfunction "VDD_19") (pintype "power_in"))
      (node (ref "U4") (pin "3") (pinfunction "VIN_3") (pintype "power_in"))
    )
    (net (code "88") (name "VCC") (class "Default")
      (node (ref "C1") (pin "1") (pinfunction "1_1") (pintype "passive"))
      (node (ref "POWER") (pin "2") (pinfunction "2_2") (pintype "passive"))
      (node (ref "U1") (pin "2") (pinfunction "VIN_2") (pintype "power_in"))
      (node (ref "U1") (pin "3") (pinfunction "VIN_3") (pintype "power_in"))
      (node (ref "U1") (pin "4") (pinfunction "VIN_4") (pintype "power_in"))
      (node (ref "V12") (pin "1") (pinfunction "P_1") (pintype "passive"))
    )
    (net (code "89") (name "unconnected-(ARDUINO-3V3-Pad2)") (class "Default")
      (node (ref "ARDUINO") (pin "2") (pinfunction "3V3_2") (pintype "output"))
    )
    (net (code "90") (name "unconnected-(ARDUINO-ADC3{slash}A3-Pad7)") (class "Default")
      (node (ref "ARDUINO") (pin "7") (pinfunction "ADC3/A3_7") (pintype "bidirectional"))
    )
    (net (code "91") (name "unconnected-(ARDUINO-ADC6{slash}A6-Pad10)") (class "Default")
      (node (ref "ARDUINO") (pin "10") (pinfunction "ADC6/A6_10") (pintype "bidirectional"))
    )
    (net (code "92") (name "unconnected-(ARDUINO-AREF-Pad3)") (class "Default")
      (node (ref "ARDUINO") (pin "3") (pinfunction "AREF_3") (pintype "input"))
    )
    (net (code "93") (name "unconnected-(ARDUINO-D0{slash}RX-Pad17)") (class "Default")
      (node (ref "ARDUINO") (pin "17") (pinfunction "D0/RX_17") (pintype "bidirectional"))
    )
    (net (code "94") (name "unconnected-(ARDUINO-D1{slash}TX-Pad16)") (class "Default")
      (node (ref "ARDUINO") (pin "16") (pinfunction "D1/TX_16") (pintype "bidirectional"))
    )
    (net (code "95") (name "unconnected-(ARDUINO-~{RESET}-Pad13)") (class "Default")
      (node (ref "ARDUINO") (pin "13") (pinfunction "~{RESET}_13") (pintype "input"))
    )
    (net (code "96") (name "unconnected-(ARDUINO-~{RESET}-Pad18)") (class "Default")
      (node (ref "ARDUINO") (pin "18") (pinfunction "~{RESET}_18") (pintype "input"))
    )
    (net (code "97") (name "unconnected-(J1-Pad33)") (class "Default")
      (node (ref "J1") (pin "33") (pinfunction "33_33") (pintype "passive"))
    )
    (net (code "98") (name "unconnected-(J1-Pad34)") (class "Default")
      (node (ref "J1") (pin "34") (pinfunction "34_34") (pintype "passive"))
    )
    (net (code "99") (name "unconnected-(J1-Pad35)") (class "Default")
      (node (ref "J1") (pin "35") (pinfunction "35_35") (pintype "passive"))
    )
    (net (code "100") (name "unconnected-(J1-Pad36)") (class "Default")
      (node (ref "J1") (pin "36") (pinfunction "36_36") (pintype "passive"))
    )
    (net (code "101") (name "unconnected-(J1-Pad37)") (class "Default")
      (node (ref "J1") (pin "37") (pinfunction "37_37") (pintype "passive"))
    )
    (net (code "102") (name "unconnected-(J1-Pad38)") (class "Default")
      (node (ref "J1") (pin "38") (pinfunction "38_38") (pintype "passive"))
    )
    (net (code "103") (name "unconnected-(J4-Pad1)") (class "Default")
      (node (ref "J4") (pin "1") (pinfunction "1_1") (pintype "passive"))
    )
    (net (code "104") (name "unconnected-(J4-Pad2)") (class "Default")
      (node (ref "J4") (pin "2") (pinfunction "2_2") (pintype "passive"))
    )
    (net (code "105") (name "unconnected-(J4-Pad3)") (class "Default")
      (node (ref "J4") (pin "3") (pinfunction "3_3") (pintype "passive"))
    )
    (net (code "106") (name "unconnected-(J4-Pad4)") (class "Default")
      (node (ref "J4") (pin "4") (pinfunction "4_4") (pintype "passive"))
    )
    (net (code "107") (name "unconnected-(J4-Pad5)") (class "Default")
      (node (ref "J4") (pin "5") (pinfunction "5_5") (pintype "passive"))
    )
    (net (code "108") (name "unconnected-(J4-Pad6)") (class "Default")
      (node (ref "J4") (pin "6") (pinfunction "6_6") (pintype "passive"))
    )
    (net (code "109") (name "unconnected-(J4-Pad7)") (class "Default")
      (node (ref "J4") (pin "7") (pinfunction "7_7") (pintype "passive"))
    )
    (net (code "110") (name "unconnected-(J4-Pad8)") (class "Default")
      (node (ref "J4") (pin "8") (pinfunction "8_8") (pintype "passive"))
    )
    (net (code "111") (name "unconnected-(J4-Pad9)") (class "Default")
      (node (ref "J4") (pin "9") (pinfunction "9_9") (pintype "passive"))
    )
    (net (code "112") (name "unconnected-(J4-Pad10)") (class "Default")
      (node (ref "J4") (pin "10") (pinfunction "10_10") (pintype "passive"))
    )
    (net (code "113") (name "unconnected-(J4-Pad11)") (class "Default")
      (node (ref "J4") (pin "11") (pinfunction "11_11") (pintype "passive"))
    )
    (net (code "114") (name "unconnected-(J4-Pad12)") (class "Default")
      (node (ref "J4") (pin "12") (pinfunction "12_12") (pintype "passive"))
    )
    (net (code "115") (name "unconnected-(J4-Pad13)") (class "Default")
      (node (ref "J4") (pin "13") (pinfunction "13_13") (pintype "passive"))
    )
    (net (code "116") (name "unconnected-(J4-Pad14)") (class "Default")
      (node (ref "J4") (pin "14") (pinfunction "14_14") (pintype "passive"))
    )
    (net (code "117") (name "unconnected-(J4-Pad15)") (class "Default")
      (node (ref "J4") (pin "15") (pinfunction "15_15") (pintype "passive"))
    )
    (net (code "118") (name "unconnected-(J4-Pad16)") (class "Default")
      (node (ref "J4") (pin "16") (pinfunction "16_16") (pintype "passive"))
    )
    (net (code "119") (name "unconnected-(J4-Pad17)") (class "Default")
      (node (ref "J4") (pin "17") (pinfunction "17_17") (pintype "passive"))
    )
    (net (code "120") (name "unconnected-(J4-Pad18)") (class "Default")
      (node (ref "J4") (pin "18") (pinfunction "18_18") (pintype "passive"))
    )
    (net (code "121") (name "unconnected-(J4-Pad19)") (class "Default")
      (node (ref "J4") (pin "19") (pinfunction "19_19") (pintype "passive"))
    )
    (net (code "122") (name "unconnected-(J4-Pad20)") (class "Default")
      (node (ref "J4") (pin "20") (pinfunction "20_20") (pintype "passive"))
    )
    (net (code "123") (name "unconnected-(J6-Pad1)") (class "Default")
      (node (ref "J6") (pin "1") (pinfunction "1_1") (pintype "passive"))
    )
    (net (code "124") (name "unconnected-(J6-Pad2)") (class "Default")
      (node (ref "J6") (pin "2") (pinfunction "2_2") (pintype "passive"))
    )
    (net (code "125") (name "unconnected-(J6-Pad3)") (class "Default")
      (node (ref "J6") (pin "3") (pinfunction "3_3") (pintype "passive"))
    )
    (net (code "126") (name "unconnected-(J6-Pad4)") (class "Default")
      (node (ref "J6") (pin "4") (pinfunction "4_4") (pintype "passive"))
    )
    (net (code "127") (name "unconnected-(J6-Pad5)") (class "Default")
      (node (ref "J6") (pin "5") (pinfunction "5_5") (pintype "passive"))
    )
    (net (code "128") (name "unconnected-(J6-Pad6)") (class "Default")
      (node (ref "J6") (pin "6") (pinfunction "6_6") (pintype "passive"))
    )
    (net (code "129") (name "unconnected-(J6-Pad7)") (class "Default")
      (node (ref "J6") (pin "7") (pinfunction "7_7") (pintype "passive"))
    )
    (net (code "130") (name "unconnected-(J6-Pad8)") (class "Default")
      (node (ref "J6") (pin "8") (pinfunction "8_8") (pintype "passive"))
    )
    (net (code "131") (name "unconnected-(J6-Pad9)") (class "Default")
      (node (ref "J6") (pin "9") (pinfunction "9_9") (pintype "passive"))
    )
    (net (code "132") (name "unconnected-(J6-Pad10)") (class "Default")
      (node (ref "J6") (pin "10") (pinfunction "10_10") (pintype "passive"))
    )
    (net (code "133") (name "unconnected-(J6-Pad11)") (class "Default")
      (node (ref "J6") (pin "11") (pinfunction "11_11") (pintype "passive"))
    )
    (net (code "134") (name "unconnected-(J6-Pad12)") (class "Default")
      (node (ref "J6") (pin "12") (pinfunction "12_12") (pintype "passive"))
    )
    (net (code "135") (name "unconnected-(J6-Pad13)") (class "Default")
      (node (ref "J6") (pin "13") (pinfunction "13_13") (pintype "passive"))
    )
    (net (code "136") (name "unconnected-(J6-Pad14)") (class "Default")
      (node (ref "J6") (pin "14") (pinfunction "14_14") (pintype "passive"))
    )
    (net (code "137") (name "unconnected-(J6-Pad15)") (class "Default")
      (node (ref "J6") (pin "15") (pinfunction "15_15") (pintype "passive"))
    )
    (net (code "138") (name "unconnected-(J6-Pad16)") (class "Default")
      (node (ref "J6") (pin "16") (pinfunction "16_16") (pintype "passive"))
    )
    (net (code "139") (name "unconnected-(J6-Pad17)") (class "Default")
      (node (ref "J6") (pin "17") (pinfunction "17_17") (pintype "passive"))
    )
    (net (code "140") (name "unconnected-(J6-Pad18)") (class "Default")
      (node (ref "J6") (pin "18") (pinfunction "18_18") (pintype "passive"))
    )
    (net (code "141") (name "unconnected-(J6-Pad19)") (class "Default")
      (node (ref "J6") (pin "19") (pinfunction "19_19") (pintype "passive"))
    )
    (net (code "142") (name "unconnected-(J6-Pad20)") (class "Default")
      (node (ref "J6") (pin "20") (pinfunction "20_20") (pintype "passive"))
    )
    (net (code "143") (name "unconnected-(U1-VADJ-Pad12)") (class "Default")
      (node (ref "U1") (pin "12") (pinfunction "VADJ_12") (pintype "bidirectional"))
    )
    (net (code "144") (name "unconnected-(U1-~{OFF}-Pad1)") (class "Default")
      (node (ref "U1") (pin "1") (pinfunction "~{OFF}_1") (pintype "bidirectional"))
    )
  )
)
